# guest_room_controller.net
KiCad netlist of a schematic drawn in EAGLE
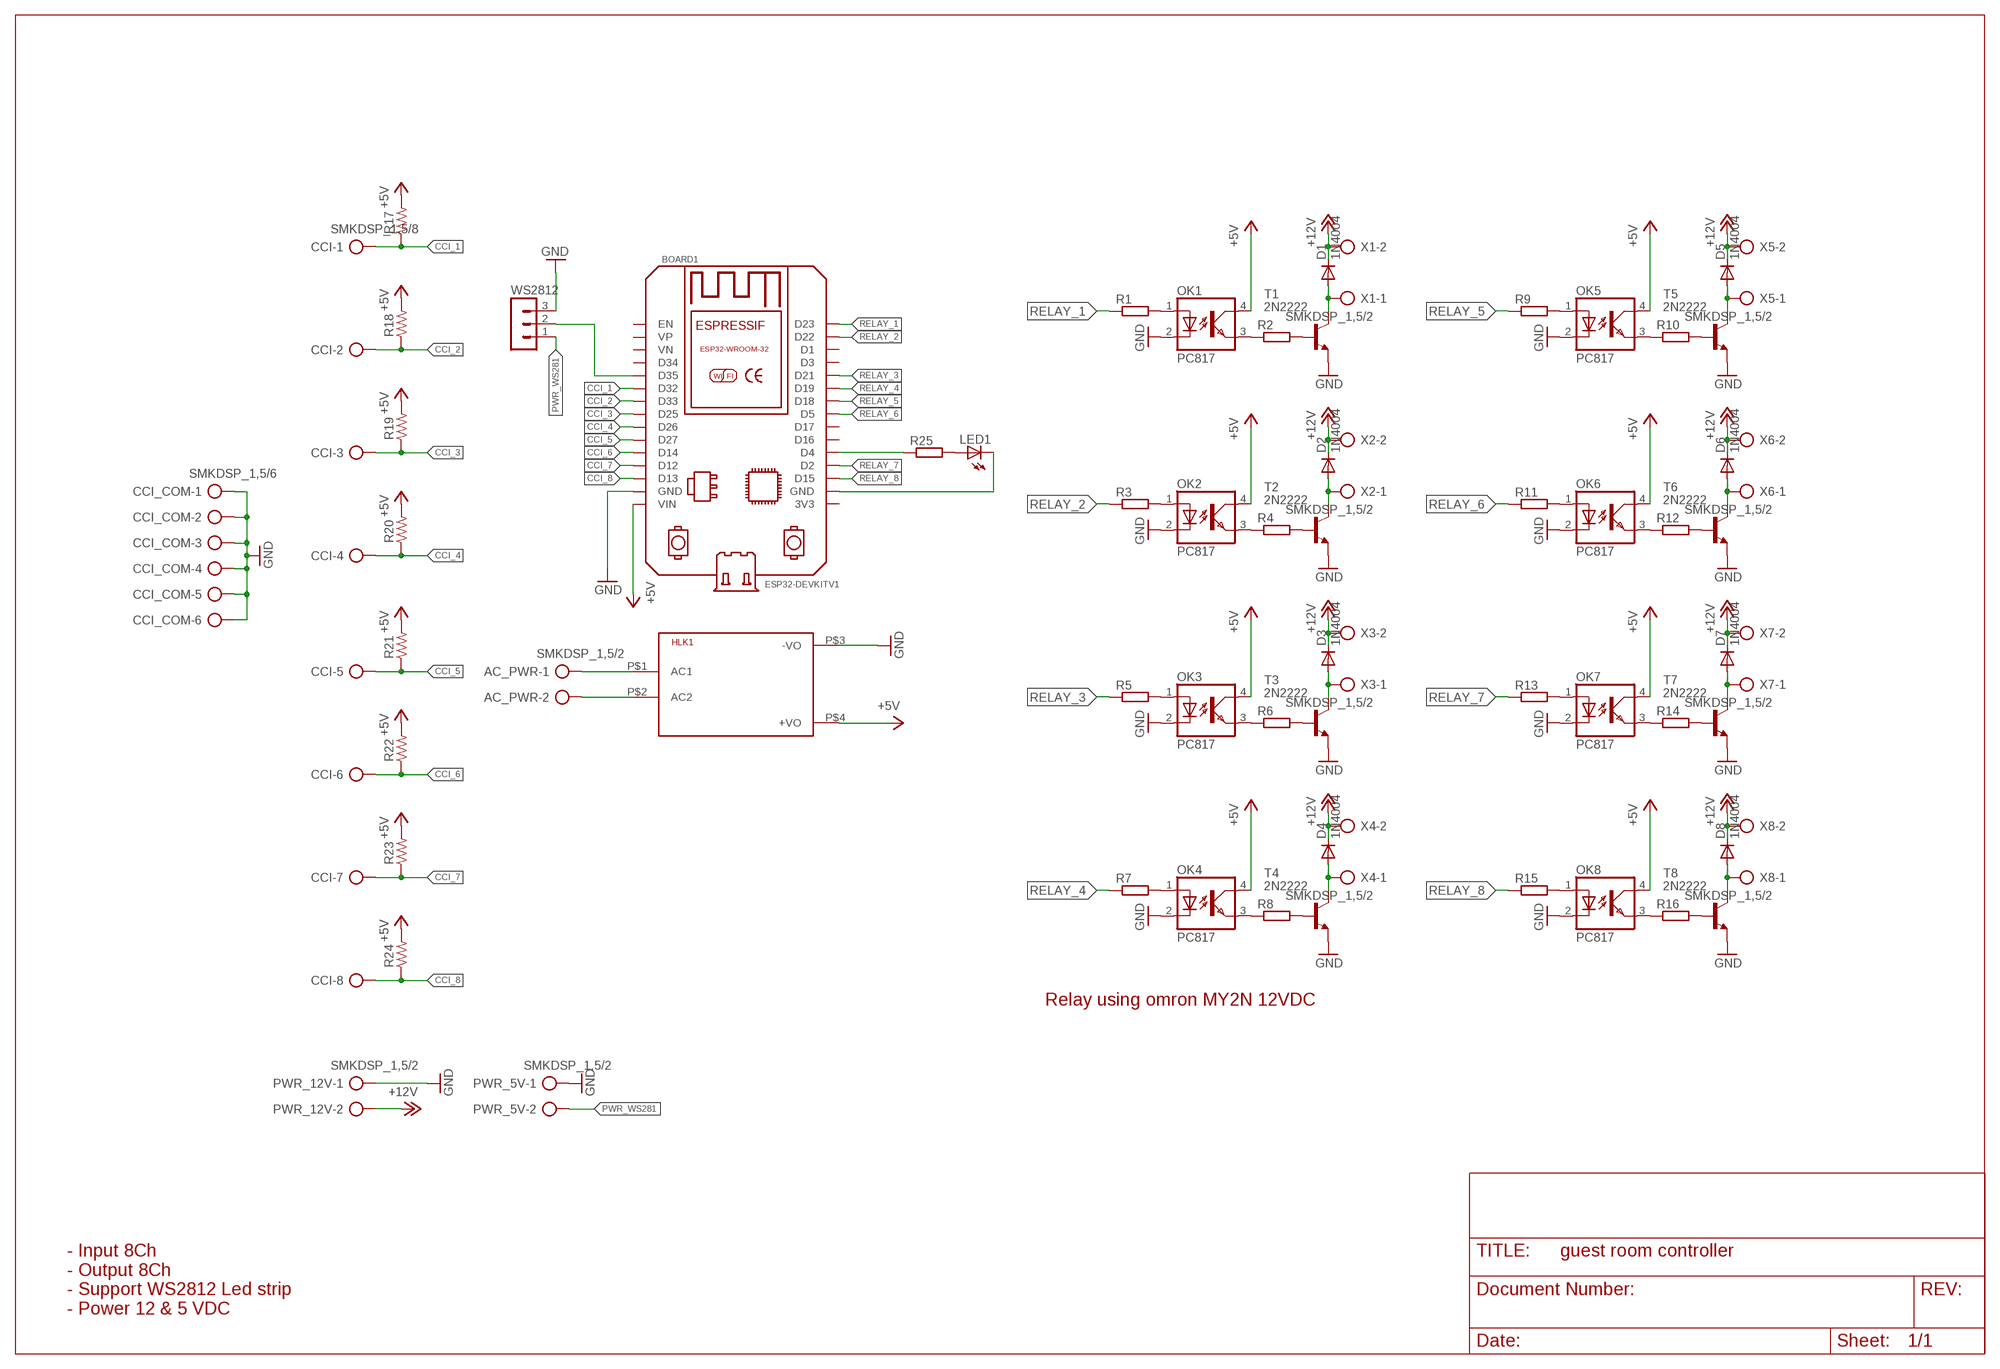
[diagram p0: schematic, sheet 1]

(export (version "E")
  (design (tool "Eeschema 10.0.6"))
  (components
    (comp (ref "AC_PWR")
      (value "SMKDSP_1,5/2")
      (footprint "eagle-import:SMKDSP_1,5_2")
      (fields (field (name "MF") "FARNELL") (field (name "MPN") "1733570"))
      (libsource (lib "eagle-import") (part "SMKDSP_1,5/2"))
    )
    (comp (ref "BOARD1")
      (value "ESP32DEVKITV1")
      (footprint "eagle-import:ESP32-DEVKITV1")
      (libsource (lib "eagle-import") (part "ESP32DEVKITV1"))
    )
    (comp (ref "CCI")
      (value "SMKDSP_1,5/8")
      (footprint "eagle-import:SMKDSP_1,5_8")
      (fields (field (name "MF") "FARNELL") (field (name "MPN") "1733635"))
      (libsource (lib "eagle-import") (part "SMKDSP_1,5/8"))
    )
    (comp (ref "CCI_COM")
      (value "SMKDSP_1,5/6")
      (footprint "eagle-import:SMKDSP_1,5_6")
      (fields (field (name "MF") "FARNELL") (field (name "MPN") "1733619"))
      (libsource (lib "eagle-import") (part "SMKDSP_1,5/6"))
    )
    (comp (ref "D1")
      (value "1N4004")
      (footprint "eagle-import:DO41-10")
      (libsource (lib "eagle-import") (part "1N4004"))
    )
    (comp (ref "D2")
      (value "1N4004")
      (footprint "eagle-import:DO41-10")
      (libsource (lib "eagle-import") (part "1N4004"))
    )
    (comp (ref "D3")
      (value "1N4004")
      (footprint "eagle-import:DO41-10")
      (libsource (lib "eagle-import") (part "1N4004"))
    )
    (comp (ref "D4")
      (value "1N4004")
      (footprint "eagle-import:DO41-10")
      (libsource (lib "eagle-import") (part "1N4004"))
    )
    (comp (ref "D5")
      (value "1N4004")
      (footprint "eagle-import:DO41-10")
      (libsource (lib "eagle-import") (part "1N4004"))
    )
    (comp (ref "D6")
      (value "1N4004")
      (footprint "eagle-import:DO41-10")
      (libsource (lib "eagle-import") (part "1N4004"))
    )
    (comp (ref "D7")
      (value "1N4004")
      (footprint "eagle-import:DO41-10")
      (libsource (lib "eagle-import") (part "1N4004"))
    )
    (comp (ref "D8")
      (value "1N4004")
      (footprint "eagle-import:DO41-10")
      (libsource (lib "eagle-import") (part "1N4004"))
    )
    (comp (ref "HLK1")
      (value "HLK-PM013W")
      (footprint "eagle-import:HLK-PM01")
      (libsource (lib "eagle-import") (part "HLK-PM013W"))
    )
    (comp (ref "LED1")
      (value "LED3MM")
      (footprint "eagle-import:LED3MM")
      (libsource (lib "eagle-import") (part "LED3MM"))
    )
    (comp (ref "OK1")
      (value "PC817")
      (footprint "eagle-import:DIL04")
      (fields (field (name "MPN") "PC817X4J000F"))
      (libsource (lib "eagle-import") (part "PC817"))
    )
    (comp (ref "OK2")
      (value "PC817")
      (footprint "eagle-import:DIL04")
      (fields (field (name "MPN") "PC817X4J000F"))
      (libsource (lib "eagle-import") (part "PC817"))
    )
    (comp (ref "OK3")
      (value "PC817")
      (footprint "eagle-import:DIL04")
      (fields (field (name "MPN") "PC817X4J000F"))
      (libsource (lib "eagle-import") (part "PC817"))
    )
    (comp (ref "OK4")
      (value "PC817")
      (footprint "eagle-import:DIL04")
      (fields (field (name "MPN") "PC817X4J000F"))
      (libsource (lib "eagle-import") (part "PC817"))
    )
    (comp (ref "OK5")
      (value "PC817")
      (footprint "eagle-import:DIL04")
      (fields (field (name "MPN") "PC817X4J000F"))
      (libsource (lib "eagle-import") (part "PC817"))
    )
    (comp (ref "OK6")
      (value "PC817")
      (footprint "eagle-import:DIL04")
      (fields (field (name "MPN") "PC817X4J000F"))
      (libsource (lib "eagle-import") (part "PC817"))
    )
    (comp (ref "OK7")
      (value "PC817")
      (footprint "eagle-import:DIL04")
      (fields (field (name "MPN") "PC817X4J000F"))
      (libsource (lib "eagle-import") (part "PC817"))
    )
    (comp (ref "OK8")
      (value "PC817")
      (footprint "eagle-import:DIL04")
      (fields (field (name "MPN") "PC817X4J000F"))
      (libsource (lib "eagle-import") (part "PC817"))
    )
    (comp (ref "PWR_5V")
      (value "SMKDSP_1,5/2")
      (footprint "eagle-import:SMKDSP_1,5_2")
      (fields (field (name "MF") "FARNELL") (field (name "MPN") "1733570"))
      (libsource (lib "eagle-import") (part "SMKDSP_1,5/2"))
    )
    (comp (ref "PWR_12V")
      (value "SMKDSP_1,5/2")
      (footprint "eagle-import:SMKDSP_1,5_2")
      (fields (field (name "MF") "FARNELL") (field (name "MPN") "1733570"))
      (libsource (lib "eagle-import") (part "SMKDSP_1,5/2"))
    )
    (comp (ref "R1")
      (value "R-EU_0207/10")
      (footprint "eagle-import:0207_10")
      (libsource (lib "eagle-import") (part "R-EU_0207/10"))
    )
    (comp (ref "R2")
      (value "R-EU_0207/10")
      (footprint "eagle-import:0207_10")
      (libsource (lib "eagle-import") (part "R-EU_0207/10"))
    )
    (comp (ref "R3")
      (value "R-EU_0207/10")
      (footprint "eagle-import:0207_10")
      (libsource (lib "eagle-import") (part "R-EU_0207/10"))
    )
    (comp (ref "R4")
      (value "R-EU_0207/10")
      (footprint "eagle-import:0207_10")
      (libsource (lib "eagle-import") (part "R-EU_0207/10"))
    )
    (comp (ref "R5")
      (value "R-EU_0207/10")
      (footprint "eagle-import:0207_10")
      (libsource (lib "eagle-import") (part "R-EU_0207/10"))
    )
    (comp (ref "R6")
      (value "R-EU_0207/10")
      (footprint "eagle-import:0207_10")
      (libsource (lib "eagle-import") (part "R-EU_0207/10"))
    )
    (comp (ref "R7")
      (value "R-EU_0207/10")
      (footprint "eagle-import:0207_10")
      (libsource (lib "eagle-import") (part "R-EU_0207/10"))
    )
    (comp (ref "R8")
      (value "R-EU_0207/10")
      (footprint "eagle-import:0207_10")
      (libsource (lib "eagle-import") (part "R-EU_0207/10"))
    )
    (comp (ref "R9")
      (value "R-EU_0207/10")
      (footprint "eagle-import:0207_10")
      (libsource (lib "eagle-import") (part "R-EU_0207/10"))
    )
    (comp (ref "R10")
      (value "R-EU_0207/10")
      (footprint "eagle-import:0207_10")
      (libsource (lib "eagle-import") (part "R-EU_0207/10"))
    )
    (comp (ref "R11")
      (value "R-EU_0207/10")
      (footprint "eagle-import:0207_10")
      (libsource (lib "eagle-import") (part "R-EU_0207/10"))
    )
    (comp (ref "R12")
      (value "R-EU_0207/10")
      (footprint "eagle-import:0207_10")
      (libsource (lib "eagle-import") (part "R-EU_0207/10"))
    )
    (comp (ref "R13")
      (value "R-EU_0207/10")
      (footprint "eagle-import:0207_10")
      (libsource (lib "eagle-import") (part "R-EU_0207/10"))
    )
    (comp (ref "R14")
      (value "R-EU_0207/10")
      (footprint "eagle-import:0207_10")
      (libsource (lib "eagle-import") (part "R-EU_0207/10"))
    )
    (comp (ref "R15")
      (value "R-EU_0207/10")
      (footprint "eagle-import:0207_10")
      (libsource (lib "eagle-import") (part "R-EU_0207/10"))
    )
    (comp (ref "R16")
      (value "R-EU_0207/10")
      (footprint "eagle-import:0207_10")
      (libsource (lib "eagle-import") (part "R-EU_0207/10"))
    )
    (comp (ref "R17")
      (value "R_1206")
      (footprint "eagle-import:R1206")
      (libsource (lib "eagle-import") (part "R_1206"))
    )
    (comp (ref "R18")
      (value "R_1206")
      (footprint "eagle-import:R1206")
      (libsource (lib "eagle-import") (part "R_1206"))
    )
    (comp (ref "R19")
      (value "R_1206")
      (footprint "eagle-import:R1206")
      (libsource (lib "eagle-import") (part "R_1206"))
    )
    (comp (ref "R20")
      (value "R_1206")
      (footprint "eagle-import:R1206")
      (libsource (lib "eagle-import") (part "R_1206"))
    )
    (comp (ref "R21")
      (value "R_1206")
      (footprint "eagle-import:R1206")
      (libsource (lib "eagle-import") (part "R_1206"))
    )
    (comp (ref "R22")
      (value "R_1206")
      (footprint "eagle-import:R1206")
      (libsource (lib "eagle-import") (part "R_1206"))
    )
    (comp (ref "R23")
      (value "R_1206")
      (footprint "eagle-import:R1206")
      (libsource (lib "eagle-import") (part "R_1206"))
    )
    (comp (ref "R24")
      (value "R_1206")
      (footprint "eagle-import:R1206")
      (libsource (lib "eagle-import") (part "R_1206"))
    )
    (comp (ref "R25")
      (value "R-EU_0207/10")
      (footprint "eagle-import:0207_10")
      (libsource (lib "eagle-import") (part "R-EU_0207/10"))
    )
    (comp (ref "T1")
      (value "2N2222")
      (footprint "eagle-import:TO18")
      (libsource (lib "eagle-import") (part "2N2222"))
    )
    (comp (ref "T2")
      (value "2N2222")
      (footprint "eagle-import:TO18")
      (libsource (lib "eagle-import") (part "2N2222"))
    )
    (comp (ref "T3")
      (value "2N2222")
      (footprint "eagle-import:TO18")
      (libsource (lib "eagle-import") (part "2N2222"))
    )
    (comp (ref "T4")
      (value "2N2222")
      (footprint "eagle-import:TO18")
      (libsource (lib "eagle-import") (part "2N2222"))
    )
    (comp (ref "T5")
      (value "2N2222")
      (footprint "eagle-import:TO18")
      (libsource (lib "eagle-import") (part "2N2222"))
    )
    (comp (ref "T6")
      (value "2N2222")
      (footprint "eagle-import:TO18")
      (libsource (lib "eagle-import") (part "2N2222"))
    )
    (comp (ref "T7")
      (value "2N2222")
      (footprint "eagle-import:TO18")
      (libsource (lib "eagle-import") (part "2N2222"))
    )
    (comp (ref "T8")
      (value "2N2222")
      (footprint "eagle-import:TO18")
      (libsource (lib "eagle-import") (part "2N2222"))
    )
    (comp (ref "WS2812")
      (value "MA03-1")
      (footprint "eagle-import:MA03-1")
      (libsource (lib "eagle-import") (part "MA03-1"))
    )
    (comp (ref "X1")
      (value "SMKDSP_1,5/2")
      (footprint "eagle-import:SMKDSP_1,5_2")
      (fields (field (name "MF") "FARNELL") (field (name "MPN") "1733570"))
      (libsource (lib "eagle-import") (part "SMKDSP_1,5/2"))
    )
    (comp (ref "X2")
      (value "SMKDSP_1,5/2")
      (footprint "eagle-import:SMKDSP_1,5_2")
      (fields (field (name "MF") "FARNELL") (field (name "MPN") "1733570"))
      (libsource (lib "eagle-import") (part "SMKDSP_1,5/2"))
    )
    (comp (ref "X3")
      (value "SMKDSP_1,5/2")
      (footprint "eagle-import:SMKDSP_1,5_2")
      (fields (field (name "MF") "FARNELL") (field (name "MPN") "1733570"))
      (libsource (lib "eagle-import") (part "SMKDSP_1,5/2"))
    )
    (comp (ref "X4")
      (value "SMKDSP_1,5/2")
      (footprint "eagle-import:SMKDSP_1,5_2")
      (fields (field (name "MF") "FARNELL") (field (name "MPN") "1733570"))
      (libsource (lib "eagle-import") (part "SMKDSP_1,5/2"))
    )
    (comp (ref "X5")
      (value "SMKDSP_1,5/2")
      (footprint "eagle-import:SMKDSP_1,5_2")
      (fields (field (name "MF") "FARNELL") (field (name "MPN") "1733570"))
      (libsource (lib "eagle-import") (part "SMKDSP_1,5/2"))
    )
    (comp (ref "X6")
      (value "SMKDSP_1,5/2")
      (footprint "eagle-import:SMKDSP_1,5_2")
      (fields (field (name "MF") "FARNELL") (field (name "MPN") "1733570"))
      (libsource (lib "eagle-import") (part "SMKDSP_1,5/2"))
    )
    (comp (ref "X7")
      (value "SMKDSP_1,5/2")
      (footprint "eagle-import:SMKDSP_1,5_2")
      (fields (field (name "MF") "FARNELL") (field (name "MPN") "1733570"))
      (libsource (lib "eagle-import") (part "SMKDSP_1,5/2"))
    )
    (comp (ref "X8")
      (value "SMKDSP_1,5/2")
      (footprint "eagle-import:SMKDSP_1,5_2")
      (fields (field (name "MF") "FARNELL") (field (name "MPN") "1733570"))
      (libsource (lib "eagle-import") (part "SMKDSP_1,5/2"))
    )
  )
  (nets
    (net (code "1") (name "+5V") (class "Default")
      (node (ref "BOARD1") (pin "VIN") (pinfunction "VIN_VIN") (pintype "bidirectional"))
      (node (ref "HLK1") (pin "P$4") (pinfunction "+VO_P$4") (pintype "bidirectional"))
      (node (ref "OK1") (pin "4") (pinfunction "COL_4") (pintype "passive"))
      (node (ref "OK2") (pin "4") (pinfunction "COL_4") (pintype "passive"))
      (node (ref "OK3") (pin "4") (pinfunction "COL_4") (pintype "passive"))
      (node (ref "OK4") (pin "4") (pinfunction "COL_4") (pintype "passive"))
      (node (ref "OK5") (pin "4") (pinfunction "COL_4") (pintype "passive"))
      (node (ref "OK6") (pin "4") (pinfunction "COL_4") (pintype "passive"))
      (node (ref "OK7") (pin "4") (pinfunction "COL_4") (pintype "passive"))
      (node (ref "OK8") (pin "4") (pinfunction "COL_4") (pintype "passive"))
      (node (ref "R17") (pin "2") (pinfunction "2_2") (pintype "passive"))
      (node (ref "R18") (pin "2") (pinfunction "2_2") (pintype "passive"))
      (node (ref "R19") (pin "2") (pinfunction "2_2") (pintype "passive"))
      (node (ref "R20") (pin "2") (pinfunction "2_2") (pintype "passive"))
      (node (ref "R21") (pin "2") (pinfunction "2_2") (pintype "passive"))
      (node (ref "R22") (pin "2") (pinfunction "2_2") (pintype "passive"))
      (node (ref "R23") (pin "2") (pinfunction "2_2") (pintype "passive"))
      (node (ref "R24") (pin "2") (pinfunction "2_2") (pintype "passive"))
    )
    (net (code "2") (name "+12V") (class "Default")
      (node (ref "D1") (pin "C") (pinfunction "C_C") (pintype "passive"))
      (node (ref "D2") (pin "C") (pinfunction "C_C") (pintype "passive"))
      (node (ref "D3") (pin "C") (pinfunction "C_C") (pintype "passive"))
      (node (ref "D4") (pin "C") (pinfunction "C_C") (pintype "passive"))
      (node (ref "D5") (pin "C") (pinfunction "C_C") (pintype "passive"))
      (node (ref "D6") (pin "C") (pinfunction "C_C") (pintype "passive"))
      (node (ref "D7") (pin "C") (pinfunction "C_C") (pintype "passive"))
      (node (ref "D8") (pin "C") (pinfunction "C_C") (pintype "passive"))
      (node (ref "PWR_12V") (pin "2") (pinfunction "KL_2") (pintype "passive"))
      (node (ref "X1") (pin "2") (pinfunction "KL_2") (pintype "passive"))
      (node (ref "X2") (pin "2") (pinfunction "KL_2") (pintype "passive"))
      (node (ref "X3") (pin "2") (pinfunction "KL_2") (pintype "passive"))
      (node (ref "X4") (pin "2") (pinfunction "KL_2") (pintype "passive"))
      (node (ref "X5") (pin "2") (pinfunction "KL_2") (pintype "passive"))
      (node (ref "X6") (pin "2") (pinfunction "KL_2") (pintype "passive"))
      (node (ref "X7") (pin "2") (pinfunction "KL_2") (pintype "passive"))
      (node (ref "X8") (pin "2") (pinfunction "KL_2") (pintype "passive"))
    )
    (net (code "3") (name "CCI_1") (class "Default")
      (node (ref "BOARD1") (pin "D32") (pinfunction "D32_D32") (pintype "bidirectional"))
      (node (ref "CCI") (pin "1") (pinfunction "KL_1") (pintype "passive"))
      (node (ref "R17") (pin "1") (pinfunction "1_1") (pintype "passive"))
    )
    (net (code "4") (name "CCI_2") (class "Default")
      (node (ref "BOARD1") (pin "D33") (pinfunction "D33_D33") (pintype "bidirectional"))
      (node (ref "CCI") (pin "2") (pinfunction "KL_2") (pintype "passive"))
      (node (ref "R18") (pin "1") (pinfunction "1_1") (pintype "passive"))
    )
    (net (code "5") (name "CCI_3") (class "Default")
      (node (ref "BOARD1") (pin "D25") (pinfunction "D25_D25") (pintype "bidirectional"))
      (node (ref "CCI") (pin "3") (pinfunction "KL_3") (pintype "passive"))
      (node (ref "R19") (pin "1") (pinfunction "1_1") (pintype "passive"))
    )
    (net (code "6") (name "CCI_4") (class "Default")
      (node (ref "BOARD1") (pin "D26") (pinfunction "D26_D26") (pintype "bidirectional"))
      (node (ref "CCI") (pin "4") (pinfunction "KL_4") (pintype "passive"))
      (node (ref "R20") (pin "1") (pinfunction "1_1") (pintype "passive"))
    )
    (net (code "7") (name "CCI_5") (class "Default")
      (node (ref "BOARD1") (pin "D27") (pinfunction "D27_D27") (pintype "bidirectional"))
      (node (ref "CCI") (pin "5") (pinfunction "KL_5") (pintype "passive"))
      (node (ref "R21") (pin "1") (pinfunction "1_1") (pintype "passive"))
    )
    (net (code "8") (name "CCI_6") (class "Default")
      (node (ref "BOARD1") (pin "D14") (pinfunction "D14_D14") (pintype "bidirectional"))
      (node (ref "CCI") (pin "6") (pinfunction "KL_6") (pintype "passive"))
      (node (ref "R22") (pin "1") (pinfunction "1_1") (pintype "passive"))
    )
    (net (code "9") (name "CCI_7") (class "Default")
      (node (ref "BOARD1") (pin "D12") (pinfunction "D12_D12") (pintype "bidirectional"))
      (node (ref "CCI") (pin "7") (pinfunction "KL_7") (pintype "passive"))
      (node (ref "R23") (pin "1") (pinfunction "1_1") (pintype "passive"))
    )
    (net (code "10") (name "CCI_8") (class "Default")
      (node (ref "BOARD1") (pin "D13") (pinfunction "D13_D13") (pintype "bidirectional"))
      (node (ref "CCI") (pin "8") (pinfunction "KL_8") (pintype "passive"))
      (node (ref "R24") (pin "1") (pinfunction "1_1") (pintype "passive"))
    )
    (net (code "11") (name "GND") (class "Default")
      (node (ref "BOARD1") (pin "GND") (pinfunction "GND_GND") (pintype "bidirectional"))
      (node (ref "CCI_COM") (pin "1") (pinfunction "KL_1") (pintype "passive"))
      (node (ref "CCI_COM") (pin "2") (pinfunction "KL_2") (pintype "passive"))
      (node (ref "CCI_COM") (pin "3") (pinfunction "KL_3") (pintype "passive"))
      (node (ref "CCI_COM") (pin "4") (pinfunction "KL_4") (pintype "passive"))
      (node (ref "CCI_COM") (pin "5") (pinfunction "KL_5") (pintype "passive"))
      (node (ref "CCI_COM") (pin "6") (pinfunction "KL_6") (pintype "passive"))
      (node (ref "HLK1") (pin "P$3") (pinfunction "-VO_P$3") (pintype "bidirectional"))
      (node (ref "OK1") (pin "2") (pinfunction "C_2") (pintype "passive"))
      (node (ref "OK2") (pin "2") (pinfunction "C_2") (pintype "passive"))
      (node (ref "OK3") (pin "2") (pinfunction "C_2") (pintype "passive"))
      (node (ref "OK4") (pin "2") (pinfunction "C_2") (pintype "passive"))
      (node (ref "OK5") (pin "2") (pinfunction "C_2") (pintype "passive"))
      (node (ref "OK6") (pin "2") (pinfunction "C_2") (pintype "passive"))
      (node (ref "OK7") (pin "2") (pinfunction "C_2") (pintype "passive"))
      (node (ref "OK8") (pin "2") (pinfunction "C_2") (pintype "passive"))
      (node (ref "PWR_12V") (pin "1") (pinfunction "KL_1") (pintype "passive"))
      (node (ref "PWR_5V") (pin "1") (pinfunction "KL_1") (pintype "passive"))
      (node (ref "T1") (pin "1") (pinfunction "E_1") (pintype "passive"))
      (node (ref "T2") (pin "1") (pinfunction "E_1") (pintype "passive"))
      (node (ref "T3") (pin "1") (pinfunction "E_1") (pintype "passive"))
      (node (ref "T4") (pin "1") (pinfunction "E_1") (pintype "passive"))
      (node (ref "T5") (pin "1") (pinfunction "E_1") (pintype "passive"))
      (node (ref "T6") (pin "1") (pinfunction "E_1") (pintype "passive"))
      (node (ref "T7") (pin "1") (pinfunction "E_1") (pintype "passive"))
      (node (ref "T8") (pin "1") (pinfunction "E_1") (pintype "passive"))
      (node (ref "WS2812") (pin "3") (pinfunction "3_3") (pintype "passive"))
    )
    (net (code "12") (name "Net-(AC_PWRA-KL)") (class "Default")
      (node (ref "AC_PWR") (pin "1") (pinfunction "KL_1") (pintype "passive"))
      (node (ref "HLK1") (pin "P$1") (pinfunction "AC1_P$1") (pintype "bidirectional"))
    )
    (net (code "13") (name "Net-(AC_PWRB-KL)") (class "Default")
      (node (ref "AC_PWR") (pin "2") (pinfunction "KL_2") (pintype "passive"))
      (node (ref "HLK1") (pin "P$2") (pinfunction "AC2_P$2") (pintype "bidirectional"))
    )
    (net (code "14") (name "Net-(BOARD1-PadD4)") (class "Default")
      (node (ref "BOARD1") (pin "D4") (pinfunction "D4_D4") (pintype "bidirectional"))
      (node (ref "R25") (pin "1") (pinfunction "1_1") (pintype "passive"))
    )
    (net (code "15") (name "Net-(BOARD1-PadD35)") (class "Default")
      (node (ref "BOARD1") (pin "D35") (pinfunction "D35_D35") (pintype "bidirectional"))
      (node (ref "WS2812") (pin "2") (pinfunction "2_2") (pintype "passive"))
    )
    (net (code "16") (name "Net-(LED1-C)") (class "Default")
      (node (ref "BOARD1") (pin "GND@1") (pinfunction "GND_GND@1") (pintype "bidirectional"))
      (node (ref "LED1") (pin "K") (pinfunction "C_K") (pintype "passive"))
    )
    (net (code "17") (name "Net-(LED1-PadA)") (class "Default")
      (node (ref "LED1") (pin "A") (pinfunction "A_A") (pintype "passive"))
      (node (ref "R25") (pin "2") (pinfunction "2_2") (pintype "passive"))
    )
    (net (code "18") (name "Net-(OK1-A)") (class "Default")
      (node (ref "OK1") (pin "1") (pinfunction "A_1") (pintype "passive"))
      (node (ref "R1") (pin "2") (pinfunction "2_2") (pintype "passive"))
    )
    (net (code "19") (name "Net-(OK1-EMIT)") (class "Default")
      (node (ref "OK1") (pin "3") (pinfunction "EMIT_3") (pintype "passive"))
      (node (ref "R2") (pin "1") (pinfunction "1_1") (pintype "passive"))
    )
    (net (code "20") (name "Net-(OK2-A)") (class "Default")
      (node (ref "OK2") (pin "1") (pinfunction "A_1") (pintype "passive"))
      (node (ref "R3") (pin "2") (pinfunction "2_2") (pintype "passive"))
    )
    (net (code "21") (name "Net-(OK2-EMIT)") (class "Default")
      (node (ref "OK2") (pin "3") (pinfunction "EMIT_3") (pintype "passive"))
      (node (ref "R4") (pin "1") (pinfunction "1_1") (pintype "passive"))
    )
    (net (code "22") (name "Net-(OK3-A)") (class "Default")
      (node (ref "OK3") (pin "1") (pinfunction "A_1") (pintype "passive"))
      (node (ref "R5") (pin "2") (pinfunction "2_2") (pintype "passive"))
    )
    (net (code "23") (name "Net-(OK3-EMIT)") (class "Default")
      (node (ref "OK3") (pin "3") (pinfunction "EMIT_3") (pintype "passive"))
      (node (ref "R6") (pin "1") (pinfunction "1_1") (pintype "passive"))
    )
    (net (code "24") (name "Net-(OK4-A)") (class "Default")
      (node (ref "OK4") (pin "1") (pinfunction "A_1") (pintype "passive"))
      (node (ref "R7") (pin "2") (pinfunction "2_2") (pintype "passive"))
    )
    (net (code "25") (name "Net-(OK4-EMIT)") (class "Default")
      (node (ref "OK4") (pin "3") (pinfunction "EMIT_3") (pintype "passive"))
      (node (ref "R8") (pin "1") (pinfunction "1_1") (pintype "passive"))
    )
    (net (code "26") (name "Net-(OK5-A)") (class "Default")
      (node (ref "OK5") (pin "1") (pinfunction "A_1") (pintype "passive"))
      (node (ref "R9") (pin "2") (pinfunction "2_2") (pintype "passive"))
    )
    (net (code "27") (name "Net-(OK5-EMIT)") (class "Default")
      (node (ref "OK5") (pin "3") (pinfunction "EMIT_3") (pintype "passive"))
      (node (ref "R10") (pin "1") (pinfunction "1_1") (pintype "passive"))
    )
    (net (code "28") (name "Net-(OK6-A)") (class "Default")
      (node (ref "OK6") (pin "1") (pinfunction "A_1") (pintype "passive"))
      (node (ref "R11") (pin "2") (pinfunction "2_2") (pintype "passive"))
    )
    (net (code "29") (name "Net-(OK6-EMIT)") (class "Default")
      (node (ref "OK6") (pin "3") (pinfunction "EMIT_3") (pintype "passive"))
      (node (ref "R12") (pin "1") (pinfunction "1_1") (pintype "passive"))
    )
    (net (code "30") (name "Net-(OK7-A)") (class "Default")
      (node (ref "OK7") (pin "1") (pinfunction "A_1") (pintype "passive"))
      (node (ref "R13") (pin "2") (pinfunction "2_2") (pintype "passive"))
    )
    (net (code "31") (name "Net-(OK7-EMIT)") (class "Default")
      (node (ref "OK7") (pin "3") (pinfunction "EMIT_3") (pintype "passive"))
      (node (ref "R14") (pin "1") (pinfunction "1_1") (pintype "passive"))
    )
    (net (code "32") (name "Net-(OK8-A)") (class "Default")
      (node (ref "OK8") (pin "1") (pinfunction "A_1") (pintype "passive"))
      (node (ref "R15") (pin "2") (pinfunction "2_2") (pintype "passive"))
    )
    (net (code "33") (name "Net-(OK8-EMIT)") (class "Default")
      (node (ref "OK8") (pin "3") (pinfunction "EMIT_3") (pintype "passive"))
      (node (ref "R16") (pin "1") (pinfunction "1_1") (pintype "passive"))
    )
    (net (code "34") (name "Net-(T1-B)") (class "Default")
      (node (ref "R2") (pin "2") (pinfunction "2_2") (pintype "passive"))
      (node (ref "T1") (pin "2") (pinfunction "B_2") (pintype "passive"))
    )
    (net (code "35") (name "Net-(T1-C)") (class "Default")
      (node (ref "D1") (pin "A") (pinfunction "A_A") (pintype "passive"))
      (node (ref "T1") (pin "3") (pinfunction "C_3") (pintype "passive"))
      (node (ref "X1") (pin "1") (pinfunction "KL_1") (pintype "passive"))
    )
    (net (code "36") (name "Net-(T2-B)") (class "Default")
      (node (ref "R4") (pin "2") (pinfunction "2_2") (pintype "passive"))
      (node (ref "T2") (pin "2") (pinfunction "B_2") (pintype "passive"))
    )
    (net (code "37") (name "Net-(T2-C)") (class "Default")
      (node (ref "D2") (pin "A") (pinfunction "A_A") (pintype "passive"))
      (node (ref "T2") (pin "3") (pinfunction "C_3") (pintype "passive"))
      (node (ref "X2") (pin "1") (pinfunction "KL_1") (pintype "passive"))
    )
    (net (code "38") (name "Net-(T3-B)") (class "Default")
      (node (ref "R6") (pin "2") (pinfunction "2_2") (pintype "passive"))
      (node (ref "T3") (pin "2") (pinfunction "B_2") (pintype "passive"))
    )
    (net (code "39") (name "Net-(T3-C)") (class "Default")
      (node (ref "D3") (pin "A") (pinfunction "A_A") (pintype "passive"))
      (node (ref "T3") (pin "3") (pinfunction "C_3") (pintype "passive"))
      (node (ref "X3") (pin "1") (pinfunction "KL_1") (pintype "passive"))
    )
    (net (code "40") (name "Net-(T4-B)") (class "Default")
      (node (ref "R8") (pin "2") (pinfunction "2_2") (pintype "passive"))
      (node (ref "T4") (pin "2") (pinfunction "B_2") (pintype "passive"))
    )
    (net (code "41") (name "Net-(T4-C)") (class "Default")
      (node (ref "D4") (pin "A") (pinfunction "A_A") (pintype "passive"))
      (node (ref "T4") (pin "3") (pinfunction "C_3") (pintype "passive"))
      (node (ref "X4") (pin "1") (pinfunction "KL_1") (pintype "passive"))
    )
    (net (code "42") (name "Net-(T5-B)") (class "Default")
      (node (ref "R10") (pin "2") (pinfunction "2_2") (pintype "passive"))
      (node (ref "T5") (pin "2") (pinfunction "B_2") (pintype "passive"))
    )
    (net (code "43") (name "Net-(T5-C)") (class "Default")
      (node (ref "D5") (pin "A") (pinfunction "A_A") (pintype "passive"))
      (node (ref "T5") (pin "3") (pinfunction "C_3") (pintype "passive"))
      (node (ref "X5") (pin "1") (pinfunction "KL_1") (pintype "passive"))
    )
    (net (code "44") (name "Net-(T6-B)") (class "Default")
      (node (ref "R12") (pin "2") (pinfunction "2_2") (pintype "passive"))
      (node (ref "T6") (pin "2") (pinfunction "B_2") (pintype "passive"))
    )
    (net (code "45") (name "Net-(T6-C)") (class "Default")
      (node (ref "D6") (pin "A") (pinfunction "A_A") (pintype "passive"))
      (node (ref "T6") (pin "3") (pinfunction "C_3") (pintype "passive"))
      (node (ref "X6") (pin "1") (pinfunction "KL_1") (pintype "passive"))
    )
    (net (code "46") (name "Net-(T7-B)") (class "Default")
      (node (ref "R14") (pin "2") (pinfunction "2_2") (pintype "passive"))
      (node (ref "T7") (pin "2") (pinfunction "B_2") (pintype "passive"))
    )
    (net (code "47") (name "Net-(T7-C)") (class "Default")
      (node (ref "D7") (pin "A") (pinfunction "A_A") (pintype "passive"))
      (node (ref "T7") (pin "3") (pinfunction "C_3") (pintype "passive"))
      (node (ref "X7") (pin "1") (pinfunction "KL_1") (pintype "passive"))
    )
    (net (code "48") (name "Net-(T8-B)") (class "Default")
      (node (ref "R16") (pin "2") (pinfunction "2_2") (pintype "passive"))
      (node (ref "T8") (pin "2") (pinfunction "B_2") (pintype "passive"))
    )
    (net (code "49") (name "Net-(T8-C)") (class "Default")
      (node (ref "D8") (pin "A") (pinfunction "A_A") (pintype "passive"))
      (node (ref "T8") (pin "3") (pinfunction "C_3") (pintype "passive"))
      (node (ref "X8") (pin "1") (pinfunction "KL_1") (pintype "passive"))
    )
    (net (code "50") (name "PWR_WS281") (class "Default")
      (node (ref "PWR_5V") (pin "2") (pinfunction "KL_2") (pintype "passive"))
      (node (ref "WS2812") (pin "1") (pinfunction "1_1") (pintype "passive"))
    )
    (net (code "51") (name "RELAY_1") (class "Default")
      (node (ref "BOARD1") (pin "D23") (pinfunction "D23_D23") (pintype "bidirectional"))
      (node (ref "R1") (pin "1") (pinfunction "1_1") (pintype "passive"))
    )
    (net (code "52") (name "RELAY_2") (class "Default")
      (node (ref "BOARD1") (pin "D22") (pinfunction "D22_D22") (pintype "bidirectional"))
      (node (ref "R3") (pin "1") (pinfunction "1_1") (pintype "passive"))
    )
    (net (code "53") (name "RELAY_3") (class "Default")
      (node (ref "BOARD1") (pin "D21") (pinfunction "D21_D21") (pintype "bidirectional"))
      (node (ref "R5") (pin "1") (pinfunction "1_1") (pintype "passive"))
    )
    (net (code "54") (name "RELAY_4") (class "Default")
      (node (ref "BOARD1") (pin "D19") (pinfunction "D19_D19") (pintype "bidirectional"))
      (node (ref "R7") (pin "1") (pinfunction "1_1") (pintype "passive"))
    )
    (net (code "55") (name "RELAY_5") (class "Default")
      (node (ref "BOARD1") (pin "D18") (pinfunction "D18_D18") (pintype "bidirectional"))
      (node (ref "R9") (pin "1") (pinfunction "1_1") (pintype "passive"))
    )
    (net (code "56") (name "RELAY_6") (class "Default")
      (node (ref "BOARD1") (pin "D5") (pinfunction "D5_D5") (pintype "bidirectional"))
      (node (ref "R11") (pin "1") (pinfunction "1_1") (pintype "passive"))
    )
    (net (code "57") (name "RELAY_7") (class "Default")
      (node (ref "BOARD1") (pin "D2") (pinfunction "D2_D2") (pintype "bidirectional"))
      (node (ref "R13") (pin "1") (pinfunction "1_1") (pintype "passive"))
    )
    (net (code "58") (name "RELAY_8") (class "Default")
      (node (ref "BOARD1") (pin "D15") (pinfunction "D15_D15") (pintype "bidirectional"))
      (node (ref "R15") (pin "1") (pinfunction "1_1") (pintype "passive"))
    )
    (net (code "59") (name "unconnected-(BOARD1-Pad3V3)") (class "Default")
      (node (ref "BOARD1") (pin "3V3") (pinfunction "3V3_3V3") (pintype "bidirectional"))
    )
    (net (code "60") (name "unconnected-(BOARD1-PadD1)") (class "Default")
      (node (ref "BOARD1") (pin "D1") (pinfunction "D1_D1") (pintype "bidirectional"))
    )
    (net (code "61") (name "unconnected-(BOARD1-PadD3)") (class "Default")
      (node (ref "BOARD1") (pin "D3") (pinfunction "D3_D3") (pintype "bidirectional"))
    )
    (net (code "62") (name "unconnected-(BOARD1-PadD16)") (class "Default")
      (node (ref "BOARD1") (pin "D16") (pinfunction "D16_D16") (pintype "bidirectional"))
    )
    (net (code "63") (name "unconnected-(BOARD1-PadD17)") (class "Default")
      (node (ref "BOARD1") (pin "D17") (pinfunction "D17_D17") (pintype "bidirectional"))
    )
    (net (code "64") (name "unconnected-(BOARD1-PadD34)") (class "Default")
      (node (ref "BOARD1") (pin "D34") (pinfunction "D34_D34") (pintype "bidirectional"))
    )
    (net (code "65") (name "unconnected-(BOARD1-PadEN)") (class "Default")
      (node (ref "BOARD1") (pin "EN") (pinfunction "EN_EN") (pintype "bidirectional"))
    )
    (net (code "66") (name "unconnected-(BOARD1-PadVN)") (class "Default")
      (node (ref "BOARD1") (pin "VN") (pinfunction "VN_VN") (pintype "bidirectional"))
    )
    (net (code "67") (name "unconnected-(BOARD1-PadVP)") (class "Default")
      (node (ref "BOARD1") (pin "VP") (pinfunction "VP_VP") (pintype "bidirectional"))
    )
  )
)
